# SENSORS.net
KiCad netlist of a schematic drawn in Altium Designer
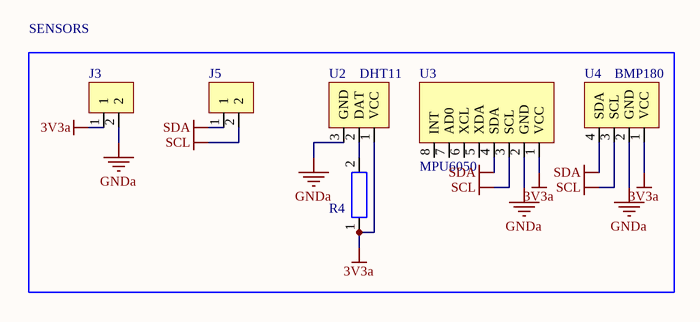
[diagram p0: SENSORS.SchDoc]

(export (version "E")
  (design (tool "Eeschema 10.0.6"))
  (components
    (comp (ref "J3")
      (value "2x1_CONN")
      (footprint "CONN2x1_2.54mm")
      (description "THT 2x1 2.54mm CONN")
      (libsource (lib "CanSat1_SchLib") (part "CONN 2x1"))
    )
    (comp (ref "J5")
      (value "2x1_CONN")
      (footprint "CONN2x1_2.54mm")
      (description "THT 2x1 2.54mm CONN")
      (libsource (lib "CanSat1_SchLib") (part "CONN 2x1"))
    )
    (comp (ref "R4")
      (value "330R")
      (footprint "THT RESISTOR")
      (description "Through-hole resistor")
      (libsource (lib "CanSat1_SchLib") (part "Resistor"))
    )
    (comp (ref "U2")
      (value "DHT11")
      (footprint "DHT11")
      (description "Humidity and temperature sensor")
      (libsource (lib "CanSat1_SchLib") (part "DHT11"))
    )
    (comp (ref "U3")
      (value "MPU6050")
      (footprint "MPU6050")
      (description "6DOF IMU sensor")
      (libsource (lib "CanSat1_SchLib") (part "MPU6050"))
    )
    (comp (ref "U4")
      (value "BMP180")
      (footprint "BMP180")
      (description "Bosch Pressure Sensor")
      (libsource (lib "CanSat1_SchLib") (part "BMP180"))
    )
  )
  (nets
    (net (code "1") (name "3V3a") (class "Default")
      (node (ref "J3") (pin "1") (pinfunction "1_1") (pintype "passive"))
      (node (ref "R4") (pin "1") (pinfunction "1_1") (pintype "passive"))
      (node (ref "U2") (pin "1") (pinfunction "VCC_1") (pintype "passive"))
      (node (ref "U3") (pin "1") (pinfunction "VCC_1") (pintype "passive"))
      (node (ref "U4") (pin "1") (pinfunction "VCC_1") (pintype "passive"))
    )
    (net (code "2") (name "GNDa") (class "Default")
      (node (ref "J3") (pin "2") (pinfunction "2_2") (pintype "passive"))
      (node (ref "U2") (pin "3") (pinfunction "GND_3") (pintype "passive"))
      (node (ref "U3") (pin "2") (pinfunction "GND_2") (pintype "passive"))
      (node (ref "U4") (pin "2") (pinfunction "GND_2") (pintype "passive"))
    )
    (net (code "3") (name "Net-(U2-DAT)") (class "Default")
      (node (ref "R4") (pin "2") (pinfunction "2_2") (pintype "passive"))
      (node (ref "U2") (pin "2") (pinfunction "DAT_2") (pintype "passive"))
    )
    (net (code "4") (name "SCL") (class "Default")
      (node (ref "J5") (pin "2") (pinfunction "2_2") (pintype "passive"))
      (node (ref "U3") (pin "3") (pinfunction "SCL_3") (pintype "passive"))
      (node (ref "U4") (pin "3") (pinfunction "SCL_3") (pintype "passive"))
    )
    (net (code "5") (name "SDA") (class "Default")
      (node (ref "J5") (pin "1") (pinfunction "1_1") (pintype "passive"))
      (node (ref "U3") (pin "4") (pinfunction "SDA_4") (pintype "passive"))
      (node (ref "U4") (pin "4") (pinfunction "SDA_4") (pintype "passive"))
    )
    (net (code "6") (name "unconnected-(U3-AD0-Pad7)") (class "Default")
      (node (ref "U3") (pin "7") (pinfunction "AD0_7") (pintype "passive"))
    )
    (net (code "7") (name "unconnected-(U3-INT-Pad8)") (class "Default")
      (node (ref "U3") (pin "8") (pinfunction "INT_8") (pintype "passive"))
    )
    (net (code "8") (name "unconnected-(U3-XCL-Pad6)") (class "Default")
      (node (ref "U3") (pin "6") (pinfunction "XCL_6") (pintype "passive"))
    )
    (net (code "9") (name "unconnected-(U3-XDA-Pad5)") (class "Default")
      (node (ref "U3") (pin "5") (pinfunction "XDA_5") (pintype "passive"))
    )
  )
)
